# TRV_SX1231_V0_1b.net
KiCad netlist of a schematic drawn in EAGLE
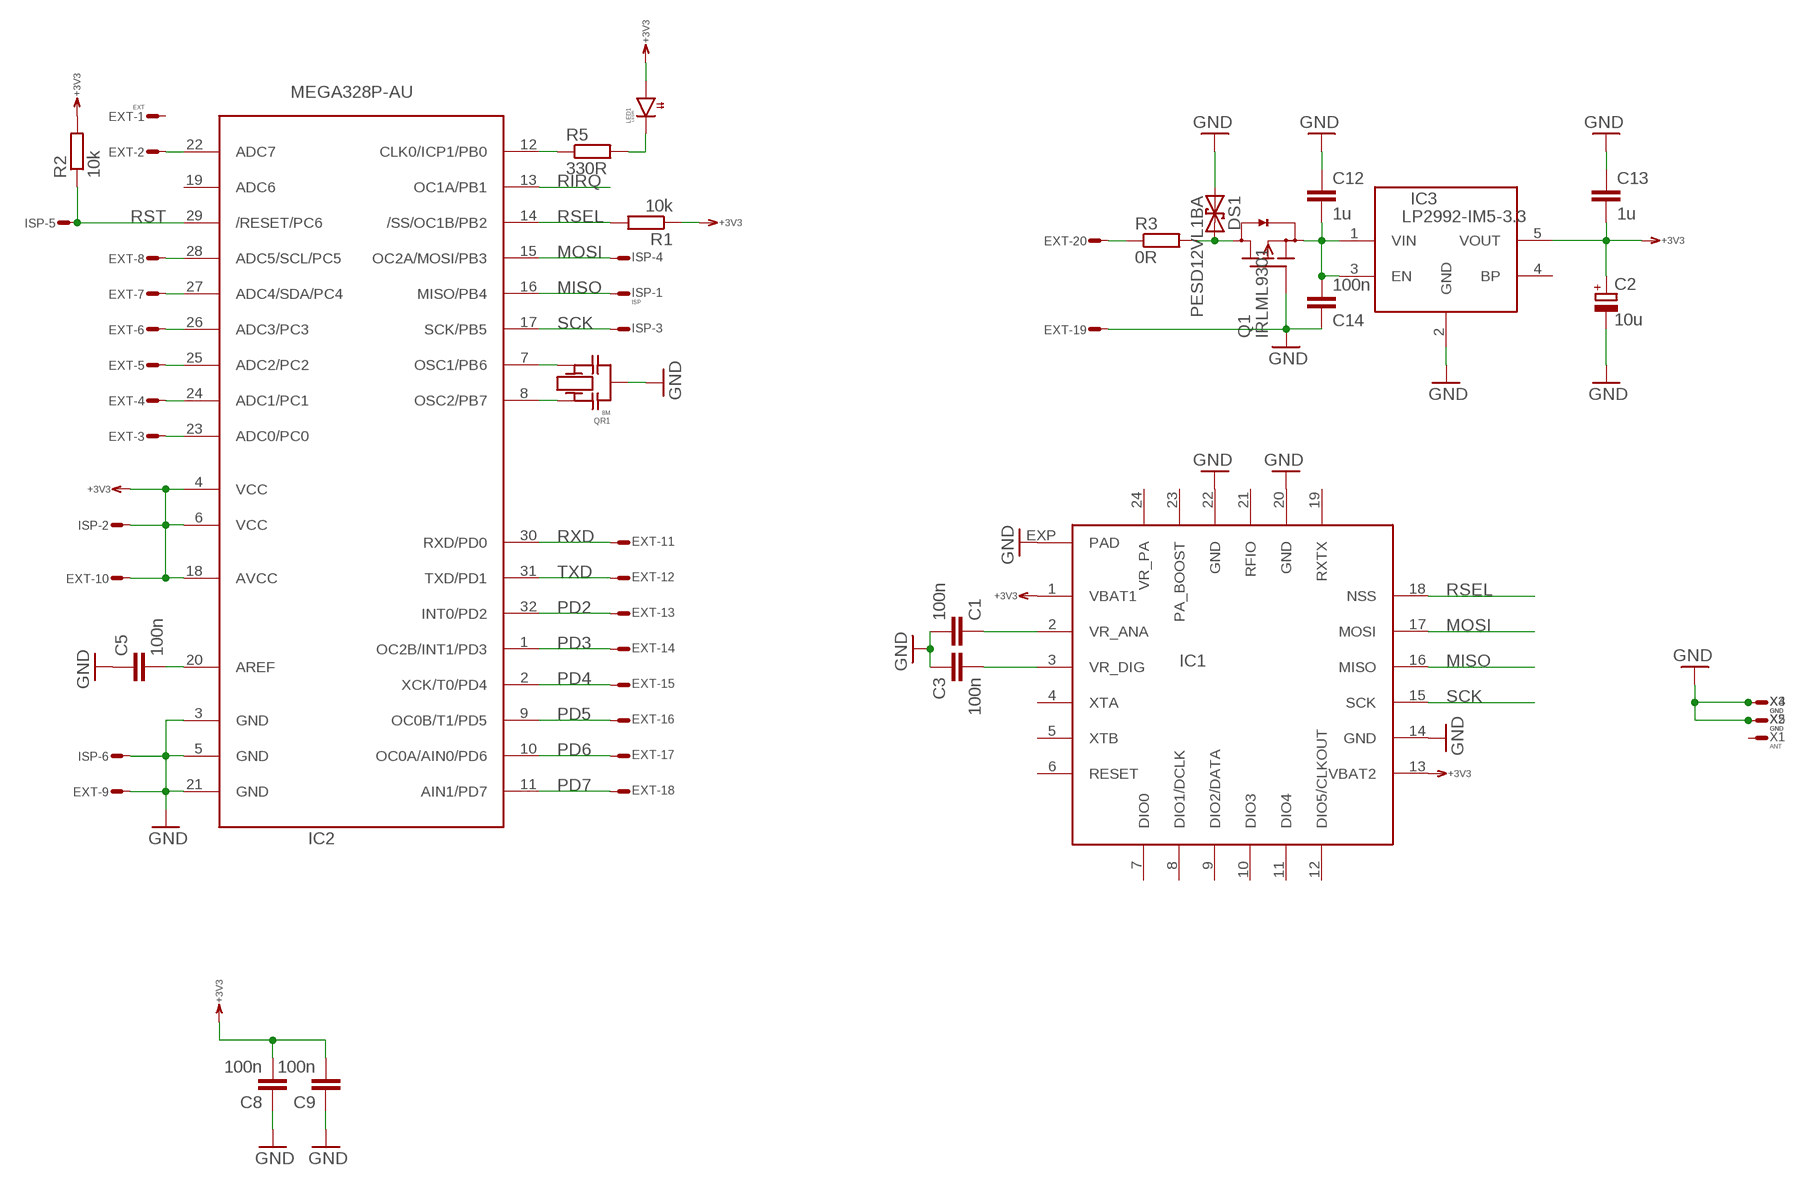
[diagram p0: schematic, sheet 1]

(export (version "E")
  (design (tool "Eeschema 10.0.6"))
  (components
    (comp (ref "C1")
      (value "100n")
      (footprint "eagle-import:0603")
      (libsource (lib "eagle-import") (part "C0603"))
    )
    (comp (ref "C2")
      (value "10u")
      (footprint "eagle-import:SMC_B")
      (libsource (lib "eagle-import") (part "C_POLSMCB"))
    )
    (comp (ref "C3")
      (value "100n")
      (footprint "eagle-import:0603")
      (libsource (lib "eagle-import") (part "C0603"))
    )
    (comp (ref "C5")
      (value "100n")
      (footprint "eagle-import:0603")
      (libsource (lib "eagle-import") (part "C0603"))
    )
    (comp (ref "C8")
      (value "100n")
      (footprint "eagle-import:0603")
      (libsource (lib "eagle-import") (part "C0603"))
    )
    (comp (ref "C9")
      (value "100n")
      (footprint "eagle-import:0603")
      (libsource (lib "eagle-import") (part "C0603"))
    )
    (comp (ref "C12")
      (value "1u")
      (footprint "eagle-import:0603")
      (libsource (lib "eagle-import") (part "C0603"))
    )
    (comp (ref "C13")
      (value "1u")
      (footprint "eagle-import:0603")
      (libsource (lib "eagle-import") (part "C0603"))
    )
    (comp (ref "C14")
      (value "100n")
      (footprint "eagle-import:0603")
      (libsource (lib "eagle-import") (part "C0603"))
    )
    (comp (ref "DS1")
      (value "PESD12VL1BA")
      (footprint "eagle-import:SOD323")
      (libsource (lib "eagle-import") (part "TVS-U323"))
    )
    (comp (ref "EXT")
      (value "EXT")
      (footprint "eagle-import:ML20S")
      (libsource (lib "eagle-import") (part "ML20?ES"))
    )
    (comp (ref "IC1")
      (value "SX1231")
      (footprint "eagle-import:QFN24")
      (libsource (lib "eagle-import") (part "SX1231"))
    )
    (comp (ref "IC2")
      (value "MEGA328P-AU")
      (footprint "eagle-import:TQFP32-08")
      (libsource (lib "eagle-import") (part "MEGA168PA"))
    )
    (comp (ref "IC3")
      (value "LP2992-IM5-3.3")
      (footprint "eagle-import:SOT23-5")
      (libsource (lib "eagle-import") (part "LDO"))
    )
    (comp (ref "ISP")
      (value "ISP")
      (footprint "eagle-import:ML6S")
      (libsource (lib "eagle-import") (part "ML6ES"))
    )
    (comp (ref "LED1")
      (value "LEDR")
      (footprint "eagle-import:0805")
      (libsource (lib "eagle-import") (part "LED0805"))
    )
    (comp (ref "Q1")
      (value "IRLML9301")
      (footprint "eagle-import:SOT23")
      (libsource (lib "eagle-import") (part "FET-PDSOT23"))
    )
    (comp (ref "QR1")
      (value "8M")
      (footprint "eagle-import:CR")
      (libsource (lib "eagle-import") (part "QRCR"))
    )
    (comp (ref "R1")
      (value "10k")
      (footprint "eagle-import:0603")
      (libsource (lib "eagle-import") (part "R0603"))
    )
    (comp (ref "R2")
      (value "10k")
      (footprint "eagle-import:0603")
      (libsource (lib "eagle-import") (part "R0603"))
    )
    (comp (ref "R3")
      (value "0R")
      (footprint "eagle-import:0603")
      (libsource (lib "eagle-import") (part "R0603"))
    )
    (comp (ref "R5")
      (value "330R")
      (footprint "eagle-import:0603")
      (libsource (lib "eagle-import") (part "R0603"))
    )
    (comp (ref "X1")
      (value "ANT")
      (footprint "eagle-import:S2.54_1.27")
      (libsource (lib "eagle-import") (part "WIREPADS2.54/1.27"))
    )
    (comp (ref "X2")
      (value "GND")
      (footprint "eagle-import:S2.54_1.27")
      (libsource (lib "eagle-import") (part "WIREPADS2.54/1.27"))
    )
    (comp (ref "X3")
      (value "GND")
      (footprint "eagle-import:S2.54_1.27")
      (libsource (lib "eagle-import") (part "WIREPADS2.54/1.27"))
    )
    (comp (ref "X4")
      (value "GND")
      (footprint "eagle-import:S2.54_1.27")
      (libsource (lib "eagle-import") (part "WIREPADS2.54/1.27"))
    )
    (comp (ref "X5")
      (value "GND")
      (footprint "eagle-import:S2.54_1.27")
      (libsource (lib "eagle-import") (part "WIREPADS2.54/1.27"))
    )
  )
  (nets
    (net (code "1") (name "+3V3") (class "Default")
      (node (ref "C13") (pin "2") (pinfunction "2_2") (pintype "passive"))
      (node (ref "C2") (pin "+") (pinfunction "+_+") (pintype "passive"))
      (node (ref "C8") (pin "2") (pinfunction "2_2") (pintype "passive"))
      (node (ref "C9") (pin "2") (pinfunction "2_2") (pintype "passive"))
      (node (ref "EXT") (pin "10") (pinfunction "S_10") (pintype "passive"))
      (node (ref "IC1") (pin "1") (pinfunction "VBAT1_1") (pintype "bidirectional"))
      (node (ref "IC1") (pin "13") (pinfunction "VBAT2_13") (pintype "bidirectional"))
      (node (ref "IC2") (pin "18") (pinfunction "AVCC_18") (pintype "bidirectional"))
      (node (ref "IC2") (pin "4") (pinfunction "VCC_4") (pintype "bidirectional"))
      (node (ref "IC2") (pin "6") (pinfunction "VCC_6") (pintype "bidirectional"))
      (node (ref "IC3") (pin "5") (pinfunction "VOUT_5") (pintype "bidirectional"))
      (node (ref "ISP") (pin "2") (pinfunction "S_2") (pintype "passive"))
      (node (ref "LED1") (pin "C") (pinfunction "A_C") (pintype "bidirectional"))
      (node (ref "R1") (pin "1") (pinfunction "1_1") (pintype "passive"))
      (node (ref "R2") (pin "2") (pinfunction "2_2") (pintype "passive"))
    )
    (net (code "2") (name "/MISO") (class "Default")
      (node (ref "IC1") (pin "16") (pinfunction "MISO_16") (pintype "output"))
      (node (ref "IC2") (pin "16") (pinfunction "MISO/PB4_16") (pintype "bidirectional"))
      (node (ref "ISP") (pin "1") (pinfunction "S_1") (pintype "passive"))
    )
    (net (code "3") (name "/MOSI") (class "Default")
      (node (ref "IC1") (pin "17") (pinfunction "MOSI_17") (pintype "input"))
      (node (ref "IC2") (pin "15") (pinfunction "OC2A/MOSI/PB3_15") (pintype "bidirectional"))
      (node (ref "ISP") (pin "4") (pinfunction "S_4") (pintype "passive"))
    )
    (net (code "4") (name "/PD2") (class "Default")
      (node (ref "EXT") (pin "13") (pinfunction "S_13") (pintype "passive"))
      (node (ref "IC2") (pin "32") (pinfunction "INT0/PD2_32") (pintype "bidirectional"))
    )
    (net (code "5") (name "/PD3") (class "Default")
      (node (ref "EXT") (pin "14") (pinfunction "S_14") (pintype "passive"))
      (node (ref "IC2") (pin "1") (pinfunction "OC2B/INT1/PD3_1") (pintype "bidirectional"))
    )
    (net (code "6") (name "/PD4") (class "Default")
      (node (ref "EXT") (pin "15") (pinfunction "S_15") (pintype "passive"))
      (node (ref "IC2") (pin "2") (pinfunction "XCK/T0/PD4_2") (pintype "bidirectional"))
    )
    (net (code "7") (name "/PD5") (class "Default")
      (node (ref "EXT") (pin "16") (pinfunction "S_16") (pintype "passive"))
      (node (ref "IC2") (pin "9") (pinfunction "OC0B/T1/PD5_9") (pintype "bidirectional"))
    )
    (net (code "8") (name "/PD6") (class "Default")
      (node (ref "EXT") (pin "17") (pinfunction "S_17") (pintype "passive"))
      (node (ref "IC2") (pin "10") (pinfunction "OC0A/AIN0/PD6_10") (pintype "bidirectional"))
    )
    (net (code "9") (name "/PD7") (class "Default")
      (node (ref "EXT") (pin "18") (pinfunction "S_18") (pintype "passive"))
      (node (ref "IC2") (pin "11") (pinfunction "AIN1/PD7_11") (pintype "bidirectional"))
    )
    (net (code "10") (name "/RIRQ") (class "Default")
      (node (ref "IC2") (pin "13") (pinfunction "OC1A/PB1_13") (pintype "bidirectional"))
    )
    (net (code "11") (name "/RSEL") (class "Default")
      (node (ref "IC1") (pin "18") (pinfunction "NSS_18") (pintype "input"))
      (node (ref "IC2") (pin "14") (pinfunction "/SS/OC1B/PB2_14") (pintype "bidirectional"))
      (node (ref "R1") (pin "2") (pinfunction "2_2") (pintype "passive"))
    )
    (net (code "12") (name "/RST") (class "Default")
      (node (ref "IC2") (pin "29") (pinfunction "/RESET/PC6_29") (pintype "bidirectional"))
      (node (ref "ISP") (pin "5") (pinfunction "S_5") (pintype "passive"))
      (node (ref "R2") (pin "1") (pinfunction "1_1") (pintype "passive"))
    )
    (net (code "13") (name "/RXD") (class "Default")
      (node (ref "EXT") (pin "11") (pinfunction "S_11") (pintype "passive"))
      (node (ref "IC2") (pin "30") (pinfunction "RXD/PD0_30") (pintype "bidirectional"))
    )
    (net (code "14") (name "/SCK") (class "Default")
      (node (ref "IC1") (pin "15") (pinfunction "SCK_15") (pintype "input"))
      (node (ref "IC2") (pin "17") (pinfunction "SCK/PB5_17") (pintype "bidirectional"))
      (node (ref "ISP") (pin "3") (pinfunction "S_3") (pintype "passive"))
    )
    (net (code "15") (name "/TXD") (class "Default")
      (node (ref "EXT") (pin "12") (pinfunction "S_12") (pintype "passive"))
      (node (ref "IC2") (pin "31") (pinfunction "TXD/PD1_31") (pintype "bidirectional"))
    )
    (net (code "16") (name "GND") (class "Default")
      (node (ref "C1") (pin "2") (pinfunction "2_2") (pintype "passive"))
      (node (ref "C12") (pin "1") (pinfunction "1_1") (pintype "passive"))
      (node (ref "C13") (pin "1") (pinfunction "1_1") (pintype "passive"))
      (node (ref "C14") (pin "1") (pinfunction "1_1") (pintype "passive"))
      (node (ref "C2") (pin "-") (pinfunction "-_-") (pintype "passive"))
      (node (ref "C3") (pin "1") (pinfunction "1_1") (pintype "passive"))
      (node (ref "C5") (pin "1") (pinfunction "1_1") (pintype "passive"))
      (node (ref "C8") (pin "1") (pinfunction "1_1") (pintype "passive"))
      (node (ref "C9") (pin "1") (pinfunction "1_1") (pintype "passive"))
      (node (ref "DS1") (pin "A") (pinfunction "1_A") (pintype "passive"))
      (node (ref "EXT") (pin "19") (pinfunction "S_19") (pintype "passive"))
      (node (ref "EXT") (pin "9") (pinfunction "S_9") (pintype "passive"))
      (node (ref "IC1") (pin "14") (pinfunction "GND_14") (pintype "bidirectional"))
      (node (ref "IC1") (pin "20") (pinfunction "GND_20") (pintype "bidirectional"))
      (node (ref "IC1") (pin "22") (pinfunction "GND_22") (pintype "bidirectional"))
      (node (ref "IC1") (pin "EXP") (pinfunction "PAD_EXP") (pintype "bidirectional"))
      (node (ref "IC2") (pin "21") (pinfunction "GND_21") (pintype "bidirectional"))
      (node (ref "IC2") (pin "3") (pinfunction "GND_3") (pintype "bidirectional"))
      (node (ref "IC2") (pin "5") (pinfunction "GND_5") (pintype "bidirectional"))
      (node (ref "IC3") (pin "2") (pinfunction "GND_2") (pintype "bidirectional"))
      (node (ref "ISP") (pin "6") (pinfunction "S_6") (pintype "passive"))
      (node (ref "Q1") (pin "1") (pinfunction "G_1") (pintype "passive"))
      (node (ref "QR1") (pin "M") (pinfunction "M_M") (pintype "passive"))
      (node (ref "X2") (pin "1") (pinfunction "S_1") (pintype "passive"))
      (node (ref "X3") (pin "1") (pinfunction "S_1") (pintype "passive"))
      (node (ref "X4") (pin "1") (pinfunction "S_1") (pintype "passive"))
      (node (ref "X5") (pin "1") (pinfunction "S_1") (pintype "passive"))
    )
    (net (code "17") (name "Net-(DS1-2)") (class "Default")
      (node (ref "DS1") (pin "C") (pinfunction "2_C") (pintype "passive"))
      (node (ref "Q1") (pin "3") (pinfunction "D_3") (pintype "passive"))
      (node (ref "R3") (pin "2") (pinfunction "2_2") (pintype "passive"))
    )
    (net (code "18") (name "Net-(EXTL-S)") (class "Default")
      (node (ref "EXT") (pin "2") (pinfunction "S_2") (pintype "passive"))
      (node (ref "IC2") (pin "22") (pinfunction "ADC7_22") (pintype "bidirectional"))
    )
    (net (code "19") (name "Net-(EXTM-S)") (class "Default")
      (node (ref "EXT") (pin "20") (pinfunction "S_20") (pintype "passive"))
      (node (ref "R3") (pin "1") (pinfunction "1_1") (pintype "passive"))
    )
    (net (code "20") (name "Net-(EXTN-S)") (class "Default")
      (node (ref "EXT") (pin "3") (pinfunction "S_3") (pintype "passive"))
      (node (ref "IC2") (pin "23") (pinfunction "ADC0/PC0_23") (pintype "bidirectional"))
    )
    (net (code "21") (name "Net-(EXTO-S)") (class "Default")
      (node (ref "EXT") (pin "4") (pinfunction "S_4") (pintype "passive"))
      (node (ref "IC2") (pin "24") (pinfunction "ADC1/PC1_24") (pintype "bidirectional"))
    )
    (net (code "22") (name "Net-(EXTP-S)") (class "Default")
      (node (ref "EXT") (pin "5") (pinfunction "S_5") (pintype "passive"))
      (node (ref "IC2") (pin "25") (pinfunction "ADC2/PC2_25") (pintype "bidirectional"))
    )
    (net (code "23") (name "Net-(EXTQ-S)") (class "Default")
      (node (ref "EXT") (pin "6") (pinfunction "S_6") (pintype "passive"))
      (node (ref "IC2") (pin "26") (pinfunction "ADC3/PC3_26") (pintype "bidirectional"))
    )
    (net (code "24") (name "Net-(EXTR-S)") (class "Default")
      (node (ref "EXT") (pin "7") (pinfunction "S_7") (pintype "passive"))
      (node (ref "IC2") (pin "27") (pinfunction "ADC4/SDA/PC4_27") (pintype "bidirectional"))
    )
    (net (code "25") (name "Net-(EXTS-S)") (class "Default")
      (node (ref "EXT") (pin "8") (pinfunction "S_8") (pintype "passive"))
      (node (ref "IC2") (pin "28") (pinfunction "ADC5/SCL/PC5_28") (pintype "bidirectional"))
    )
    (net (code "26") (name "Net-(IC1-VR_ANA)") (class "Default")
      (node (ref "C1") (pin "1") (pinfunction "1_1") (pintype "passive"))
      (node (ref "IC1") (pin "2") (pinfunction "VR_ANA_2") (pintype "bidirectional"))
    )
    (net (code "27") (name "Net-(IC1-VR_DIG)") (class "Default")
      (node (ref "C3") (pin "2") (pinfunction "2_2") (pintype "passive"))
      (node (ref "IC1") (pin "3") (pinfunction "VR_DIG_3") (pintype "bidirectional"))
    )
    (net (code "28") (name "Net-(IC2-AREF)") (class "Default")
      (node (ref "C5") (pin "2") (pinfunction "2_2") (pintype "passive"))
      (node (ref "IC2") (pin "20") (pinfunction "AREF_20") (pintype "bidirectional"))
    )
    (net (code "29") (name "Net-(IC2-CLK0{slash}ICP1{slash}PB0)") (class "Default")
      (node (ref "IC2") (pin "12") (pinfunction "CLK0/ICP1/PB0_12") (pintype "bidirectional"))
      (node (ref "R5") (pin "1") (pinfunction "1_1") (pintype "passive"))
    )
    (net (code "30") (name "Net-(IC2-OSC1{slash}PB6)") (class "Default")
      (node (ref "IC2") (pin "7") (pinfunction "OSC1/PB6_7") (pintype "bidirectional"))
      (node (ref "QR1") (pin "2") (pinfunction "2_2") (pintype "passive"))
    )
    (net (code "31") (name "Net-(IC2-OSC2{slash}PB7)") (class "Default")
      (node (ref "IC2") (pin "8") (pinfunction "OSC2/PB7_8") (pintype "bidirectional"))
      (node (ref "QR1") (pin "1") (pinfunction "1_1") (pintype "passive"))
    )
    (net (code "32") (name "Net-(IC3-EN)") (class "Default")
      (node (ref "C12") (pin "2") (pinfunction "2_2") (pintype "passive"))
      (node (ref "C14") (pin "2") (pinfunction "2_2") (pintype "passive"))
      (node (ref "IC3") (pin "1") (pinfunction "VIN_1") (pintype "bidirectional"))
      (node (ref "IC3") (pin "3") (pinfunction "EN_3") (pintype "bidirectional"))
      (node (ref "Q1") (pin "2") (pinfunction "S_2") (pintype "passive"))
    )
    (net (code "33") (name "Net-(LED1-C)") (class "Default")
      (node (ref "LED1") (pin "A") (pinfunction "C_A") (pintype "bidirectional"))
      (node (ref "R5") (pin "2") (pinfunction "2_2") (pintype "passive"))
    )
    (net (code "34") (name "unconnected-(EXTA-S-Pad1)") (class "Default")
      (node (ref "EXT") (pin "1") (pinfunction "S_1") (pintype "passive"))
    )
    (net (code "35") (name "unconnected-(IC1-DIO0-Pad7)") (class "Default")
      (node (ref "IC1") (pin "7") (pinfunction "DIO0_7") (pintype "bidirectional"))
    )
    (net (code "36") (name "unconnected-(IC1-DIO1{slash}DCLK-Pad8)") (class "Default")
      (node (ref "IC1") (pin "8") (pinfunction "DIO1/DCLK_8") (pintype "bidirectional"))
    )
    (net (code "37") (name "unconnected-(IC1-DIO2{slash}DATA-Pad9)") (class "Default")
      (node (ref "IC1") (pin "9") (pinfunction "DIO2/DATA_9") (pintype "bidirectional"))
    )
    (net (code "38") (name "unconnected-(IC1-DIO3-Pad10)") (class "Default")
      (node (ref "IC1") (pin "10") (pinfunction "DIO3_10") (pintype "bidirectional"))
    )
    (net (code "39") (name "unconnected-(IC1-DIO4-Pad11)") (class "Default")
      (node (ref "IC1") (pin "11") (pinfunction "DIO4_11") (pintype "bidirectional"))
    )
    (net (code "40") (name "unconnected-(IC1-DIO5{slash}CLKOUT-Pad12)") (class "Default")
      (node (ref "IC1") (pin "12") (pinfunction "DIO5/CLKOUT_12") (pintype "bidirectional"))
    )
    (net (code "41") (name "unconnected-(IC1-PA_BOOST-Pad23)") (class "Default")
      (node (ref "IC1") (pin "23") (pinfunction "PA_BOOST_23") (pintype "output"))
    )
    (net (code "42") (name "unconnected-(IC1-RESET-Pad6)") (class "Default")
      (node (ref "IC1") (pin "6") (pinfunction "RESET_6") (pintype "bidirectional"))
    )
    (net (code "43") (name "unconnected-(IC1-RFIO-Pad21)") (class "Default")
      (node (ref "IC1") (pin "21") (pinfunction "RFIO_21") (pintype "bidirectional"))
    )
    (net (code "44") (name "unconnected-(IC1-RXTX-Pad19)") (class "Default")
      (node (ref "IC1") (pin "19") (pinfunction "RXTX_19") (pintype "output"))
    )
    (net (code "45") (name "unconnected-(IC1-VR_PA-Pad24)") (class "Default")
      (node (ref "IC1") (pin "24") (pinfunction "VR_PA_24") (pintype "bidirectional"))
    )
    (net (code "46") (name "unconnected-(IC1-XTA-Pad4)") (class "Default")
      (node (ref "IC1") (pin "4") (pinfunction "XTA_4") (pintype "bidirectional"))
    )
    (net (code "47") (name "unconnected-(IC1-XTB-Pad5)") (class "Default")
      (node (ref "IC1") (pin "5") (pinfunction "XTB_5") (pintype "bidirectional"))
    )
    (net (code "48") (name "unconnected-(IC2-ADC6-Pad19)") (class "Default")
      (node (ref "IC2") (pin "19") (pinfunction "ADC6_19") (pintype "bidirectional"))
    )
    (net (code "49") (name "unconnected-(IC3-BP-Pad4)") (class "Default")
      (node (ref "IC3") (pin "4") (pinfunction "BP_4") (pintype "bidirectional"))
    )
    (net (code "50") (name "unconnected-(X1-S-Pad1)") (class "Default")
      (node (ref "X1") (pin "1") (pinfunction "S_1") (pintype "passive"))
    )
  )
)
